# ESP8266ModuleEV1.net
KiCad netlist of a schematic drawn in EAGLE
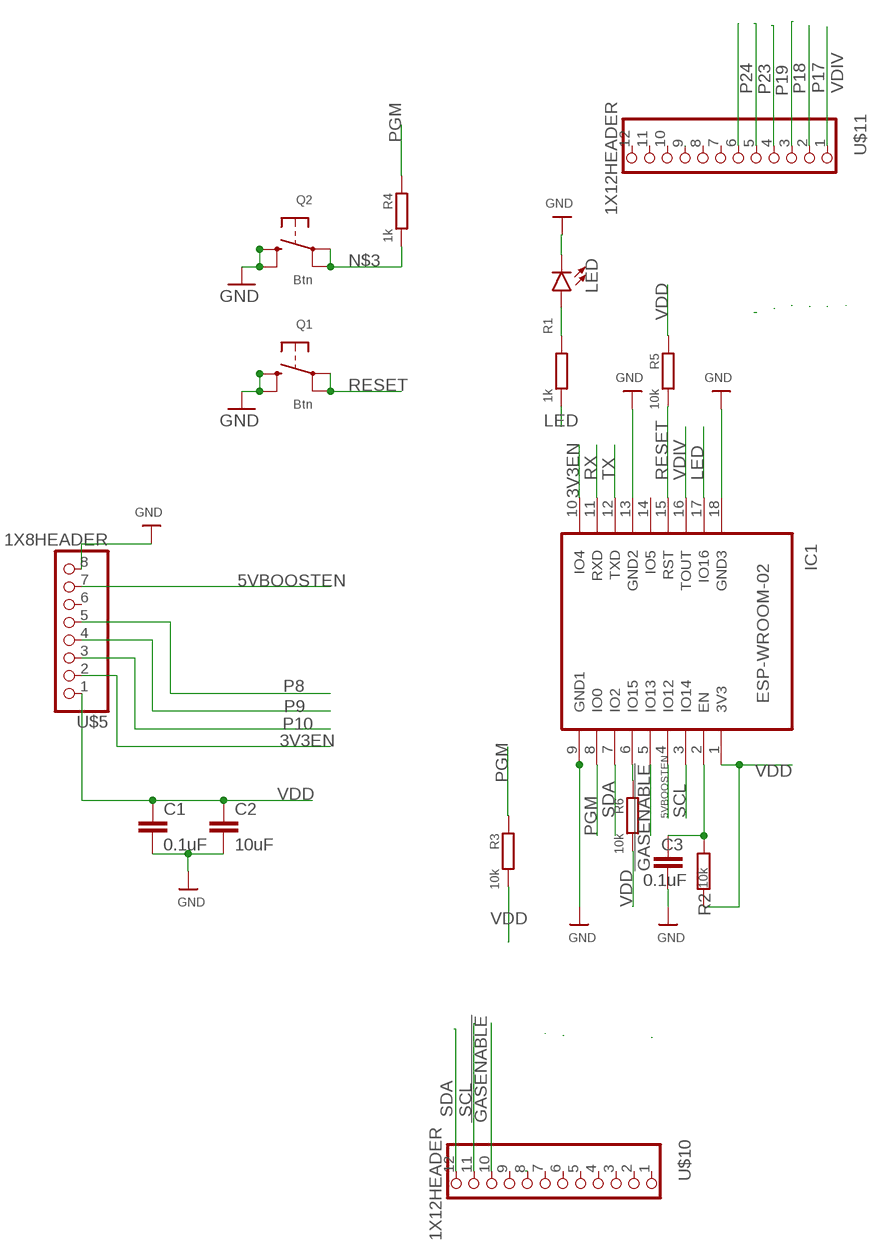
[diagram p0: schematic, sheet 1]

(export (version "E")
  (design (tool "Eeschema 10.0.6"))
  (components
    (comp (ref "C1")
      (value "0.1uF")
      (footprint "eagle-import:RESC0402_N")
      (libsource (lib "eagle-import") (part "CAPACITOR_0402_N"))
    )
    (comp (ref "C2")
      (value "10uF")
      (footprint "eagle-import:RESC0402_N")
      (libsource (lib "eagle-import") (part "CAPACITOR_0402_N"))
    )
    (comp (ref "C3")
      (value "0.1uF")
      (footprint "eagle-import:RESC0402_N")
      (libsource (lib "eagle-import") (part "CAPACITOR_0402_N"))
    )
    (comp (ref "IC1")
      (value "ESP-WROOM-02")
      (footprint "eagle-import:ESP-WROOM-02")
      (libsource (lib "eagle-import") (part "ESP-WROOM-02"))
    )
    (comp (ref "LED")
      (value "LED0603")
      (footprint "eagle-import:LED-0603")
      (libsource (lib "eagle-import") (part "LED0603"))
    )
    (comp (ref "Q1")
      (value "Btn")
      (footprint "eagle-import:BTN_KMR2_4.6X2.8")
      (libsource (lib "eagle-import") (part "SWITCH_TACT_SMT4.6X2.8"))
    )
    (comp (ref "Q2")
      (value "Btn")
      (footprint "eagle-import:BTN_KMR2_4.6X2.8")
      (libsource (lib "eagle-import") (part "SWITCH_TACT_SMT4.6X2.8"))
    )
    (comp (ref "R1")
      (value "1k")
      (footprint "eagle-import:R0402")
      (libsource (lib "eagle-import") (part "RESR0402"))
    )
    (comp (ref "R2")
      (value "10k")
      (footprint "eagle-import:RESC0402_N")
      (libsource (lib "eagle-import") (part "RESISTOR_0402_N"))
    )
    (comp (ref "R3")
      (value "10k")
      (footprint "eagle-import:R0402")
      (libsource (lib "eagle-import") (part "RESR0402"))
    )
    (comp (ref "R4")
      (value "1k")
      (footprint "eagle-import:R0402")
      (libsource (lib "eagle-import") (part "RESR0402"))
    )
    (comp (ref "R5")
      (value "10k")
      (footprint "eagle-import:R0402")
      (libsource (lib "eagle-import") (part "RESR0402"))
    )
    (comp (ref "R6")
      (value "10k")
      (footprint "eagle-import:R0402")
      (libsource (lib "eagle-import") (part "RESR0402"))
    )
    (comp (ref "U$5")
      (value "1X8HEADER")
      (footprint "eagle-import:8X1")
      (libsource (lib "eagle-import") (part "1X8HEADER"))
    )
    (comp (ref "U$10")
      (value "1X12HEADER")
      (footprint "eagle-import:1X12")
      (libsource (lib "eagle-import") (part "1X12HEADER"))
    )
    (comp (ref "U$11")
      (value "1X12HEADER")
      (footprint "eagle-import:1X12")
      (libsource (lib "eagle-import") (part "1X12HEADER"))
    )
  )
  (nets
    (net (code "1") (name "/3V3EN") (class "Default")
      (node (ref "IC1") (pin "10") (pinfunction "IO4_10") (pintype "bidirectional"))
      (node (ref "U$5") (pin "2") (pinfunction "2_2") (pintype "passive"))
    )
    (net (code "2") (name "/5VBOOSTEN") (class "Default")
      (node (ref "IC1") (pin "4") (pinfunction "IO12_4") (pintype "bidirectional"))
      (node (ref "U$5") (pin "7") (pinfunction "7_7") (pintype "passive"))
    )
    (net (code "3") (name "/LED") (class "Default")
      (node (ref "IC1") (pin "17") (pinfunction "IO16_17") (pintype "bidirectional"))
      (node (ref "R1") (pin "2") (pinfunction "2_2") (pintype "bidirectional"))
    )
    (net (code "4") (name "/N$3") (class "Default")
      (node (ref "Q2") (pin "A") (pinfunction "P_A") (pintype "passive"))
      (node (ref "Q2") (pin "A'") (pinfunction "P1_A'") (pintype "passive"))
      (node (ref "R4") (pin "2") (pinfunction "2_2") (pintype "bidirectional"))
    )
    (net (code "5") (name "/P8") (class "Default")
      (node (ref "U$5") (pin "5") (pinfunction "5_5") (pintype "passive"))
    )
    (net (code "6") (name "/P9") (class "Default")
      (node (ref "U$5") (pin "4") (pinfunction "4_4") (pintype "passive"))
    )
    (net (code "7") (name "/P10") (class "Default")
      (node (ref "U$5") (pin "3") (pinfunction "3_3") (pintype "passive"))
    )
    (net (code "8") (name "/P17") (class "Default")
      (node (ref "U$11") (pin "2") (pinfunction "2_2") (pintype "passive"))
    )
    (net (code "9") (name "/P18") (class "Default")
      (node (ref "U$11") (pin "3") (pinfunction "3_3") (pintype "passive"))
    )
    (net (code "10") (name "/P19") (class "Default")
      (node (ref "U$11") (pin "4") (pinfunction "4_4") (pintype "passive"))
    )
    (net (code "11") (name "/P23") (class "Default")
      (node (ref "U$11") (pin "5") (pinfunction "5_5") (pintype "passive"))
    )
    (net (code "12") (name "/P24") (class "Default")
      (node (ref "U$11") (pin "6") (pinfunction "6_6") (pintype "passive"))
    )
    (net (code "14") (name "/P29") (class "Default")
      (node (ref "U$10") (pin "8") (pinfunction "8_8") (pintype "passive"))
    )
    (net (code "15") (name "/PGM") (class "Default")
      (node (ref "IC1") (pin "8") (pinfunction "IO0_8") (pintype "bidirectional"))
      (node (ref "R3") (pin "1") (pinfunction "1_1") (pintype "bidirectional"))
      (node (ref "R4") (pin "1") (pinfunction "1_1") (pintype "bidirectional"))
    )
    (net (code "16") (name "/RESET") (class "Default")
      (node (ref "IC1") (pin "15") (pinfunction "RST_15") (pintype "bidirectional"))
      (node (ref "Q1") (pin "A") (pinfunction "P_A") (pintype "passive"))
      (node (ref "Q1") (pin "A'") (pinfunction "P1_A'") (pintype "passive"))
      (node (ref "R5") (pin "2") (pinfunction "2_2") (pintype "bidirectional"))
    )
    (net (code "17") (name "/RX") (class "Default")
      (node (ref "IC1") (pin "11") (pinfunction "RXD_11") (pintype "bidirectional"))
    )
    (net (code "18") (name "/SCL") (class "Default")
      (node (ref "IC1") (pin "3") (pinfunction "IO14_3") (pintype "bidirectional"))
      (node (ref "U$10") (pin "11") (pinfunction "11_11") (pintype "passive"))
    )
    (net (code "19") (name "/SDA") (class "Default")
      (node (ref "IC1") (pin "7") (pinfunction "IO2_7") (pintype "bidirectional"))
      (node (ref "U$10") (pin "12") (pinfunction "12_12") (pintype "passive"))
    )
    (net (code "20") (name "/TX") (class "Default")
      (node (ref "IC1") (pin "12") (pinfunction "TXD_12") (pintype "bidirectional"))
    )
    (net (code "21") (name "/VDD") (class "Default")
      (node (ref "C1") (pin "1") (pinfunction "1_1") (pintype "passive"))
      (node (ref "C2") (pin "1") (pinfunction "1_1") (pintype "passive"))
      (node (ref "IC1") (pin "1") (pinfunction "3V3_1") (pintype "power_in"))
      (node (ref "R2") (pin "1") (pinfunction "1_1") (pintype "passive"))
      (node (ref "R3") (pin "2") (pinfunction "2_2") (pintype "bidirectional"))
      (node (ref "R5") (pin "1") (pinfunction "1_1") (pintype "bidirectional"))
      (node (ref "R6") (pin "2") (pinfunction "2_2") (pintype "bidirectional"))
      (node (ref "U$5") (pin "1") (pinfunction "1_1") (pintype "passive"))
    )
    (net (code "22") (name "/VDIV") (class "Default")
      (node (ref "IC1") (pin "16") (pinfunction "TOUT_16") (pintype "bidirectional"))
      (node (ref "U$11") (pin "1") (pinfunction "1_1") (pintype "passive"))
    )
    (net (code "23") (name "/~{GASENABLE}") (class "Default")
      (node (ref "IC1") (pin "5") (pinfunction "IO13_5") (pintype "bidirectional"))
      (node (ref "U$10") (pin "10") (pinfunction "10_10") (pintype "passive"))
    )
    (net (code "24") (name "GND") (class "Default")
      (node (ref "C1") (pin "2") (pinfunction "2_2") (pintype "passive"))
      (node (ref "C2") (pin "2") (pinfunction "2_2") (pintype "passive"))
      (node (ref "C3") (pin "2") (pinfunction "2_2") (pintype "passive"))
      (node (ref "IC1") (pin "13") (pinfunction "GND2_13") (pintype "power_in"))
      (node (ref "IC1") (pin "18") (pinfunction "GND3_18") (pintype "power_in"))
      (node (ref "IC1") (pin "19") (pinfunction "GND0_19") (pintype "power_in"))
      (node (ref "IC1") (pin "9") (pinfunction "GND1_9") (pintype "power_in"))
      (node (ref "LED") (pin "C") (pinfunction "C_C") (pintype "passive"))
      (node (ref "Q1") (pin "B") (pinfunction "S_B") (pintype "passive"))
      (node (ref "Q1") (pin "B'") (pinfunction "S1_B'") (pintype "passive"))
      (node (ref "Q2") (pin "B") (pinfunction "S_B") (pintype "passive"))
      (node (ref "Q2") (pin "B'") (pinfunction "S1_B'") (pintype "passive"))
      (node (ref "U$5") (pin "8") (pinfunction "8_8") (pintype "passive"))
    )
    (net (code "25") (name "Net-(IC1-EN)") (class "Default")
      (node (ref "C3") (pin "1") (pinfunction "1_1") (pintype "passive"))
      (node (ref "IC1") (pin "2") (pinfunction "EN_2") (pintype "bidirectional"))
      (node (ref "R2") (pin "2") (pinfunction "2_2") (pintype "passive"))
    )
    (net (code "26") (name "Net-(IC1-IO15)") (class "Default")
      (node (ref "IC1") (pin "6") (pinfunction "IO15_6") (pintype "bidirectional"))
      (node (ref "R6") (pin "1") (pinfunction "1_1") (pintype "bidirectional"))
    )
    (net (code "27") (name "Net-(LED-PadA)") (class "Default")
      (node (ref "LED") (pin "A") (pinfunction "A_A") (pintype "passive"))
      (node (ref "R1") (pin "1") (pinfunction "1_1") (pintype "bidirectional"))
    )
    (net (code "28") (name "unconnected-(IC1-IO5-Pad14)") (class "Default")
      (node (ref "IC1") (pin "14") (pinfunction "IO5_14") (pintype "open_collector"))
    )
    (net (code "29") (name "unconnected-(U$5-Pad6)") (class "Default")
      (node (ref "U$5") (pin "6") (pinfunction "6_6") (pintype "passive"))
    )
    (net (code "30") (name "unconnected-(U$10-Pad1)") (class "Default")
      (node (ref "U$10") (pin "1") (pinfunction "1_1") (pintype "passive"))
    )
    (net (code "31") (name "unconnected-(U$10-Pad2)") (class "Default")
      (node (ref "U$10") (pin "2") (pinfunction "2_2") (pintype "passive"))
    )
    (net (code "32") (name "unconnected-(U$10-Pad3)") (class "Default")
      (node (ref "U$10") (pin "3") (pinfunction "3_3") (pintype "passive"))
    )
    (net (code "33") (name "unconnected-(U$10-Pad4)") (class "Default")
      (node (ref "U$10") (pin "4") (pinfunction "4_4") (pintype "passive"))
    )
    (net (code "34") (name "unconnected-(U$10-Pad5)") (class "Default")
      (node (ref "U$10") (pin "5") (pinfunction "5_5") (pintype "passive"))
    )
    (net (code "35") (name "unconnected-(U$10-Pad6)") (class "Default")
      (node (ref "U$10") (pin "6") (pinfunction "6_6") (pintype "passive"))
    )
    (net (code "36") (name "unconnected-(U$10-Pad7)") (class "Default")
      (node (ref "U$10") (pin "7") (pinfunction "7_7") (pintype "passive"))
    )
    (net (code "37") (name "unconnected-(U$10-Pad9)") (class "Default")
      (node (ref "U$10") (pin "9") (pinfunction "9_9") (pintype "passive"))
    )
    (net (code "38") (name "unconnected-(U$11-Pad7)") (class "Default")
      (node (ref "U$11") (pin "7") (pinfunction "7_7") (pintype "passive"))
    )
    (net (code "39") (name "unconnected-(U$11-Pad8)") (class "Default")
      (node (ref "U$11") (pin "8") (pinfunction "8_8") (pintype "passive"))
    )
    (net (code "40") (name "unconnected-(U$11-Pad9)") (class "Default")
      (node (ref "U$11") (pin "9") (pinfunction "9_9") (pintype "passive"))
    )
    (net (code "41") (name "unconnected-(U$11-Pad10)") (class "Default")
      (node (ref "U$11") (pin "10") (pinfunction "10_10") (pintype "passive"))
    )
    (net (code "42") (name "unconnected-(U$11-Pad11)") (class "Default")
      (node (ref "U$11") (pin "11") (pinfunction "11_11") (pintype "passive"))
    )
    (net (code "43") (name "unconnected-(U$11-Pad12)") (class "Default")
      (node (ref "U$11") (pin "12") (pinfunction "12_12") (pintype "passive"))
    )
  )
)
